# 5V.net
KiCad netlist of a schematic drawn in Altium Designer
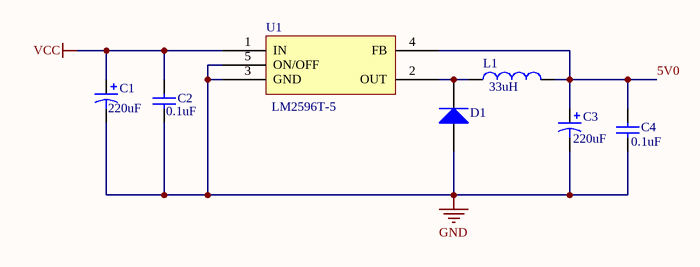
[diagram p0: 5V变压模块.SchDoc]

(export (version "E")
  (design (tool "Eeschema 10.0.6"))
  (components
    (comp (ref "C1")
      (value "220uF")
      (footprint "C0805")
      (description "Polarized Capacitor (Surface Mount)")
      (fields (field (name "Comment") "Cap Pol3") (field (name "PUBLISHER") "Altium Limited"))
      (libsource (lib "Miscellaneous Devices") (part "Cap Pol3"))
    )
    (comp (ref "C2")
      (value "0.1uF")
      (footprint "C1206")
      (description "Capacitor (Semiconductor SIM Model)")
      (fields (field (name "Comment") "Cap Semi") (field (name "PUBLISHER") "Altium Limited"))
      (libsource (lib "Miscellaneous Devices") (part "Cap Semi"))
    )
    (comp (ref "C3")
      (value "220uF")
      (footprint "C0805")
      (description "Polarized Capacitor (Surface Mount)")
      (fields (field (name "Comment") "Cap Pol3") (field (name "PUBLISHER") "Altium Limited"))
      (libsource (lib "Miscellaneous Devices") (part "Cap Pol3"))
    )
    (comp (ref "C4")
      (value "0.1uF")
      (footprint "C1206")
      (description "Capacitor (Semiconductor SIM Model)")
      (fields (field (name "Comment") "Cap Semi") (field (name "PUBLISHER") "Altium Limited"))
      (libsource (lib "Miscellaneous Devices") (part "Cap Semi"))
    )
    (comp (ref "D1")
      (value "Diode BAT18")
      (footprint "SOT-23_N")
      (description "Low-Loss RF Switching Diode")
      (fields (field (name "PUBLISHER") "Altium Limited"))
      (libsource (lib "Miscellaneous Devices") (part "Diode BAT18"))
    )
    (comp (ref "L1")
      (value "33uH")
      (footprint "0402-A")
      (description "Inductor")
      (fields (field (name "PUBLISHER") "Altium Limited"))
      (libsource (lib "Miscellaneous Devices") (part "Inductor"))
    )
    (comp (ref "U1") (value "LM2596T-5") (libsource (lib "LM2596T") (part "LM2596T")))
  )
  (nets
    (net (code "1") (name "/5V0") (class "Default")
      (node (ref "C3") (pin "1") (pinfunction "1_1") (pintype "passive"))
      (node (ref "C4") (pin "2") (pinfunction "2_2") (pintype "passive"))
      (node (ref "L1") (pin "2") (pinfunction "2_2") (pintype "passive"))
      (node (ref "U1") (pin "4") (pinfunction "FB_4") (pintype "passive"))
    )
    (net (code "2") (name "GND") (class "Default")
      (node (ref "C1") (pin "2") (pinfunction "2_2") (pintype "passive"))
      (node (ref "C2") (pin "1") (pinfunction "1_1") (pintype "passive"))
      (node (ref "C3") (pin "2") (pinfunction "2_2") (pintype "passive"))
      (node (ref "C4") (pin "1") (pinfunction "1_1") (pintype "passive"))
      (node (ref "D1") (pin "1") (pinfunction "A_1") (pintype "passive"))
      (node (ref "U1") (pin "3") (pinfunction "GND_3") (pintype "passive"))
      (node (ref "U1") (pin "5") (pinfunction "ON/OFF_5") (pintype "passive"))
    )
    (net (code "3") (name "Net-(D1-K)") (class "Default")
      (node (ref "D1") (pin "3") (pinfunction "K_3") (pintype "passive"))
      (node (ref "L1") (pin "1") (pinfunction "1_1") (pintype "passive"))
      (node (ref "U1") (pin "2") (pinfunction "OUT_2") (pintype "passive"))
    )
    (net (code "4") (name "VCC") (class "Default")
      (node (ref "C1") (pin "1") (pinfunction "1_1") (pintype "passive"))
      (node (ref "C2") (pin "2") (pinfunction "2_2") (pintype "passive"))
      (node (ref "U1") (pin "1") (pinfunction "IN_1") (pintype "passive"))
    )
  )
)
